# Aux_kicker.net
KiCad netlist of a schematic drawn in EAGLE
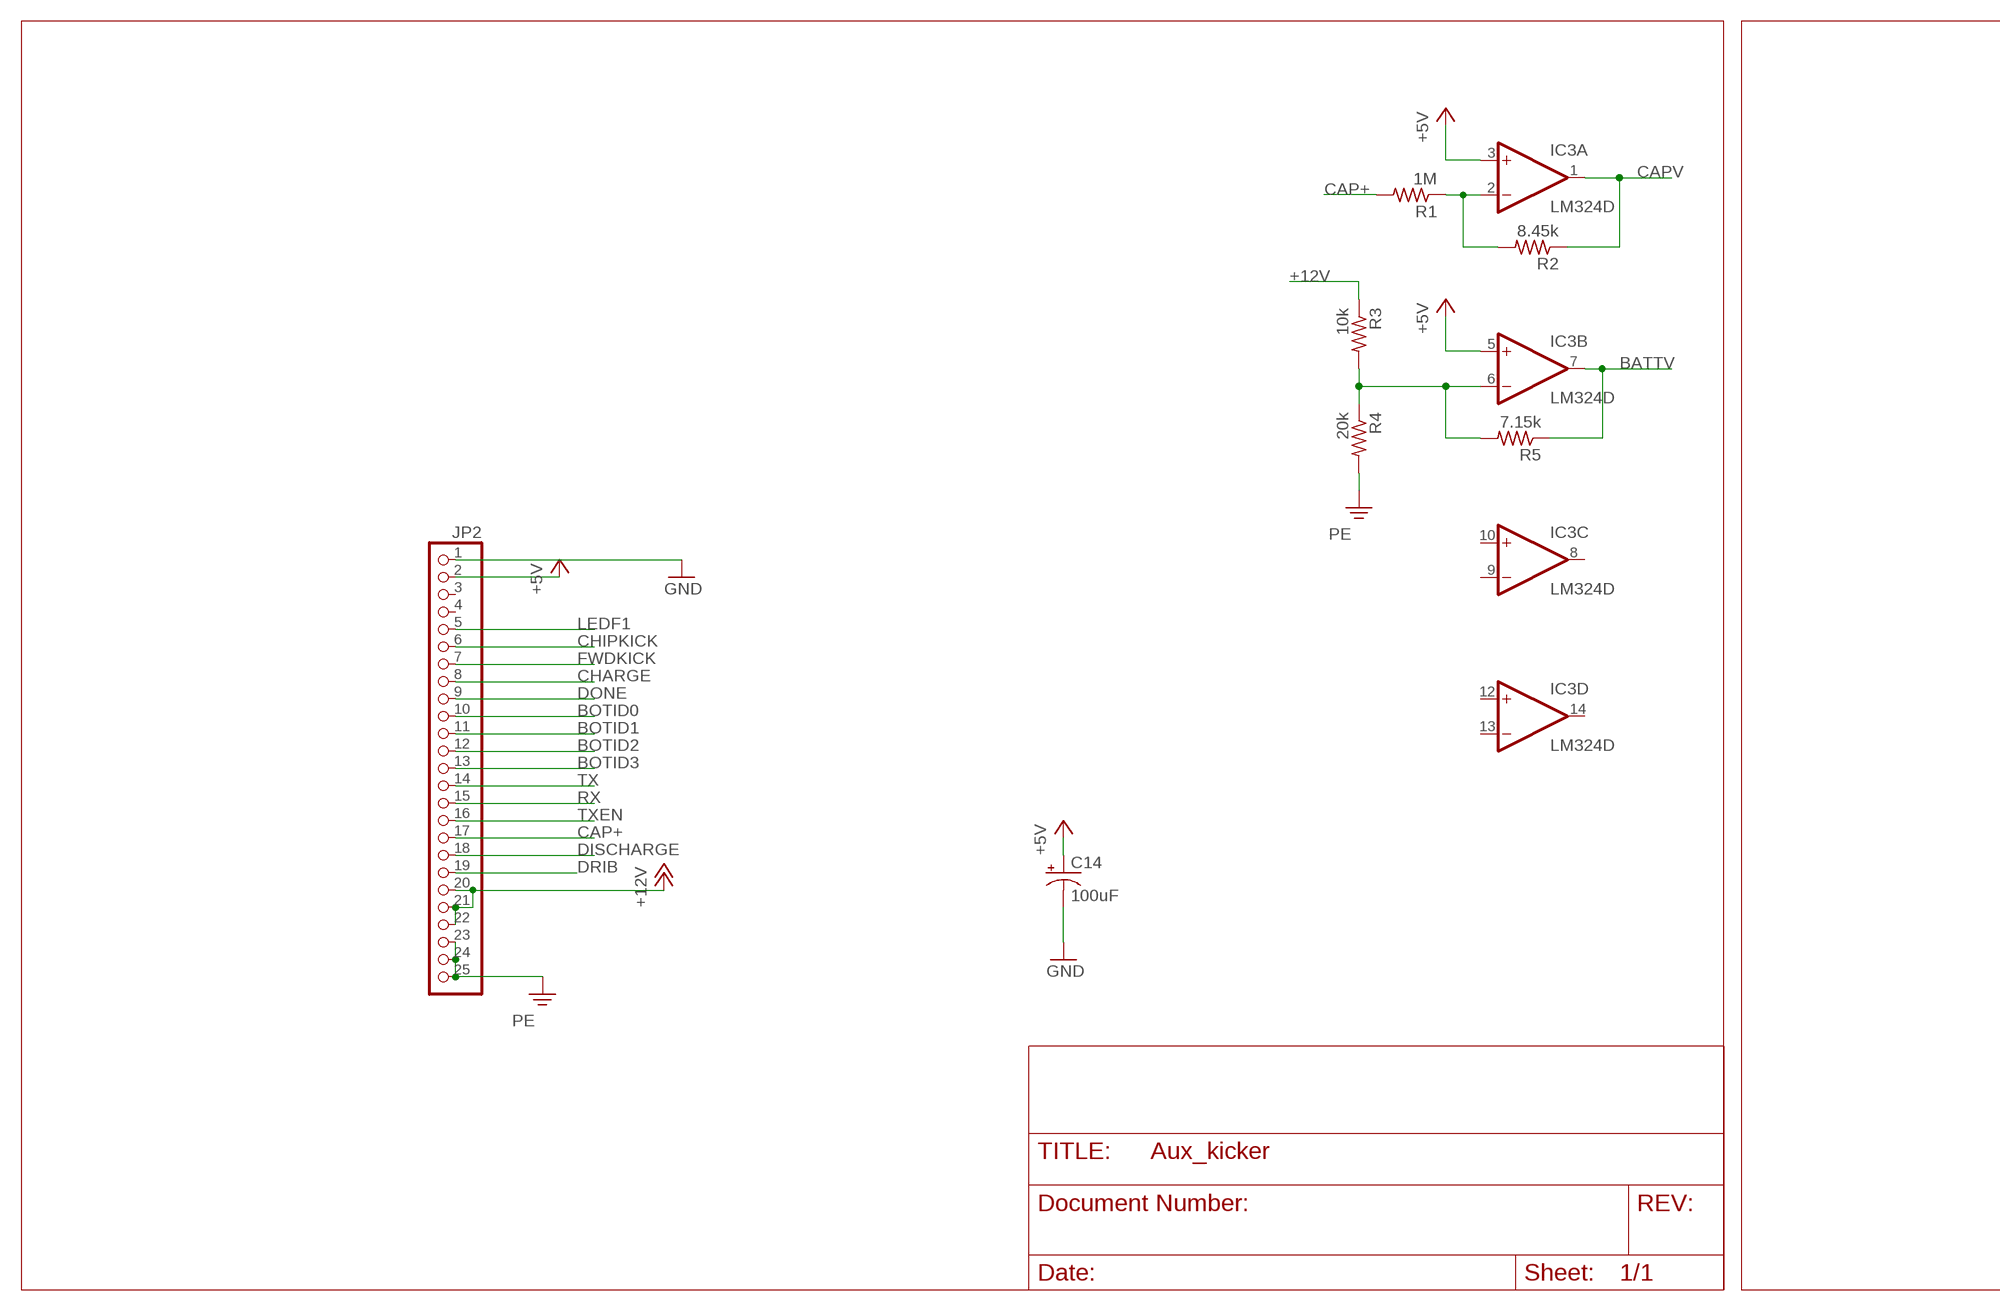
[diagram p0: schematic, sheet 1, part 1 of 2]
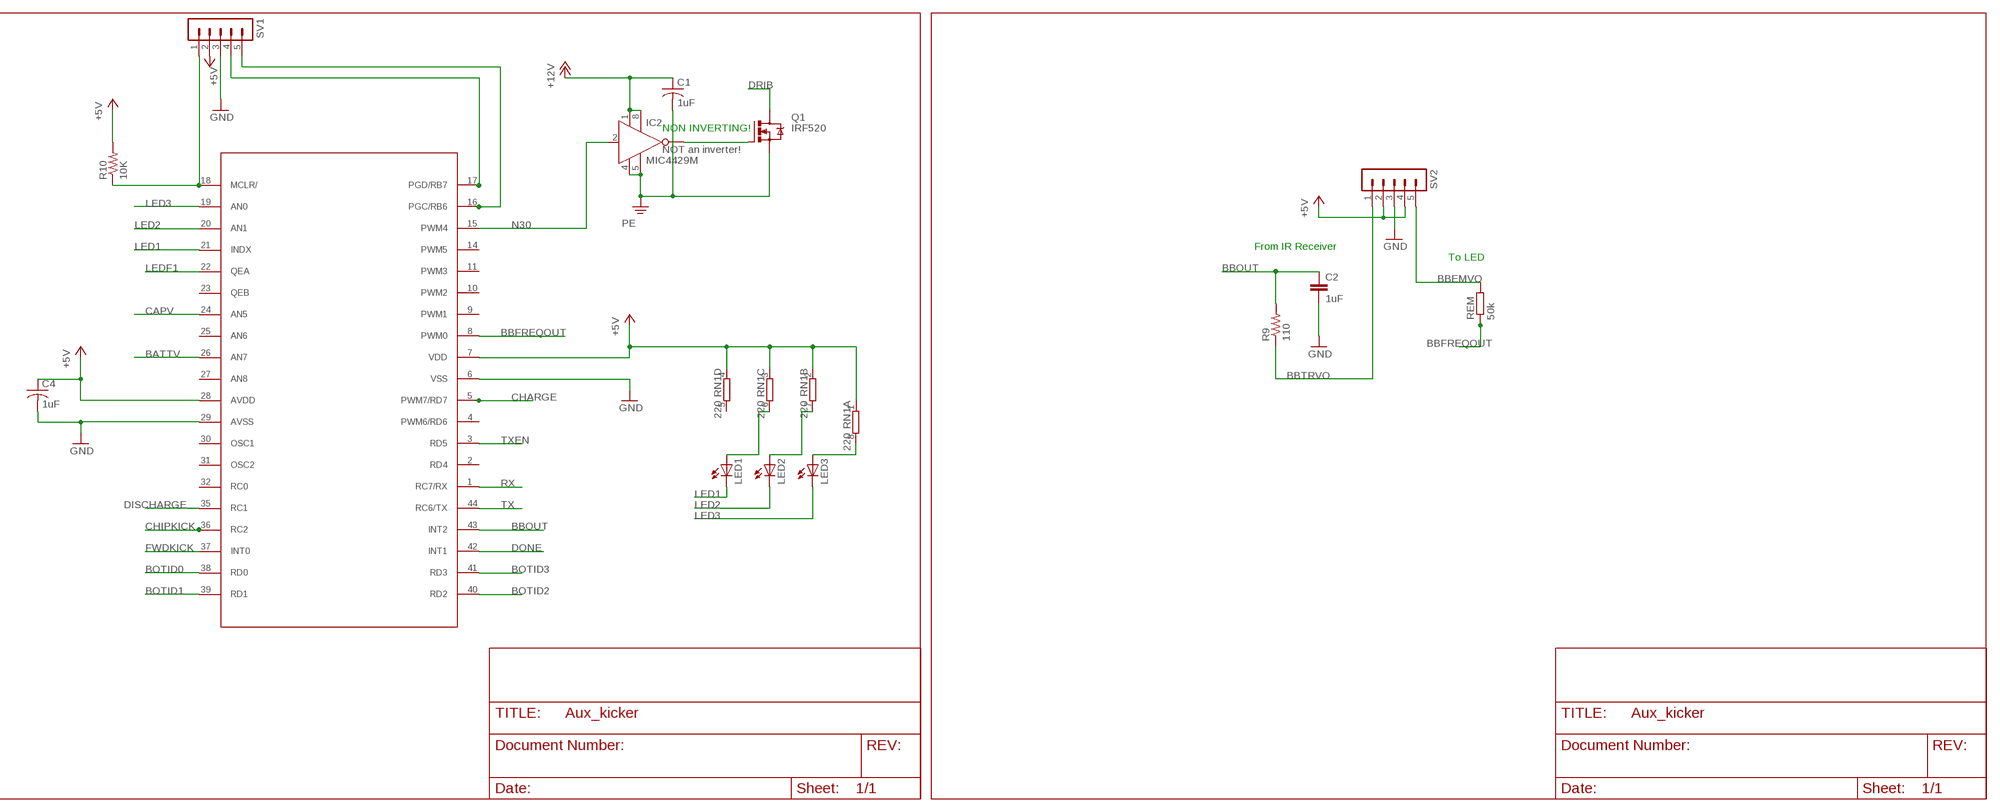
[diagram p1: schematic, sheet 1, part 2 of 2]

(export (version "E")
  (design (tool "Eeschema 10.0.6"))
  (components
    (comp (ref "C1")
      (value "1uF")
      (footprint "eagle-import:C0805")
      (libsource (lib "eagle-import") (part "C-USC0805"))
    )
    (comp (ref "C2")
      (value "1uF")
      (footprint "eagle-import:C0805")
      (libsource (lib "eagle-import") (part "C-EUC0805"))
    )
    (comp (ref "C4")
      (value "1uF")
      (footprint "eagle-import:C0805")
      (libsource (lib "eagle-import") (part "C-USC0805"))
    )
    (comp (ref "C14")
      (value "100uF")
      (footprint "eagle-import:E2,5-5")
      (libsource (lib "eagle-import") (part "CPOL-USE2.5-5"))
    )
    (comp (ref "IC1")
      (value "PIC18F4431S")
      (footprint "eagle-import:TQFP44")
      (libsource (lib "eagle-import") (part "PIC18F4431S"))
    )
    (comp (ref "IC2")
      (value "MIC4429M")
      (footprint "eagle-import:SO-08")
      (libsource (lib "eagle-import") (part "MIC4429M"))
    )
    (comp (ref "IC3")
      (value "LM324D")
      (footprint "eagle-import:SO14")
      (libsource (lib "eagle-import") (part "LM324D"))
    )
    (comp (ref "JP2")
      (value "PINHD-1X25")
      (footprint "eagle-import:1X25")
      (libsource (lib "eagle-import") (part "PINHD-1X25"))
    )
    (comp (ref "LED1")
      (value "LEDCHIPLED_0805")
      (footprint "eagle-import:CHIPLED_0805")
      (libsource (lib "eagle-import") (part "LEDCHIPLED_0805"))
    )
    (comp (ref "LED2")
      (value "LEDCHIPLED_0805")
      (footprint "eagle-import:CHIPLED_0805")
      (libsource (lib "eagle-import") (part "LEDCHIPLED_0805"))
    )
    (comp (ref "LED3")
      (value "LEDCHIPLED_0805")
      (footprint "eagle-import:CHIPLED_0805")
      (libsource (lib "eagle-import") (part "LEDCHIPLED_0805"))
    )
    (comp (ref "Q1")
      (value "IRF520")
      (footprint "eagle-import:TO220BV")
      (libsource (lib "eagle-import") (part "IRF520"))
    )
    (comp (ref "R1")
      (value "1M")
      (footprint "eagle-import:R0805")
      (libsource (lib "eagle-import") (part "R-US_R0805"))
    )
    (comp (ref "R2")
      (value "8.45k")
      (footprint "eagle-import:R0805")
      (libsource (lib "eagle-import") (part "R-US_R0805"))
    )
    (comp (ref "R3")
      (value "10k")
      (footprint "eagle-import:R0805")
      (libsource (lib "eagle-import") (part "R-US_R0805"))
    )
    (comp (ref "R4")
      (value "20k")
      (footprint "eagle-import:R0805")
      (libsource (lib "eagle-import") (part "R-US_R0805"))
    )
    (comp (ref "R5")
      (value "7.15k")
      (footprint "eagle-import:R0805")
      (libsource (lib "eagle-import") (part "R-US_R0805"))
    )
    (comp (ref "R9")
      (value "110")
      (footprint "eagle-import:R0805")
      (libsource (lib "eagle-import") (part "R-US_R0805"))
    )
    (comp (ref "R10")
      (value "10K")
      (footprint "eagle-import:R0805")
      (libsource (lib "eagle-import") (part "R-US_R0805"))
    )
    (comp (ref "REM")
      (value "50k")
      (footprint "eagle-import:R0805")
      (libsource (lib "eagle-import") (part "R-EU_R0805"))
    )
    (comp (ref "RN1")
      (value "220")
      (footprint "eagle-import:0603-ARC")
      (libsource (lib "eagle-import") (part "4R-N0603-ARC"))
    )
    (comp (ref "SV1")
      (value "MA05-1")
      (footprint "eagle-import:MA05-1")
      (libsource (lib "eagle-import") (part "MA05-1"))
    )
    (comp (ref "SV2")
      (value "MA05-1")
      (footprint "eagle-import:MA05-1")
      (libsource (lib "eagle-import") (part "MA05-1"))
    )
  )
  (nets
    (net (code "1") (name "+5V") (class "Default")
      (node (ref "C14") (pin "+") (pinfunction "+_+") (pintype "passive"))
      (node (ref "C4") (pin "1") (pinfunction "1_1") (pintype "passive"))
      (node (ref "IC1") (pin "28") (pinfunction "AVDD_28") (pintype "bidirectional"))
      (node (ref "IC1") (pin "7") (pinfunction "VDD_7") (pintype "bidirectional"))
      (node (ref "IC3") (pin "3") (pinfunction "+IN_3") (pintype "input"))
      (node (ref "IC3") (pin "5") (pinfunction "+IN_5") (pintype "input"))
      (node (ref "JP2") (pin "2") (pinfunction "2_2") (pintype "passive"))
      (node (ref "R10") (pin "2") (pinfunction "2_2") (pintype "passive"))
      (node (ref "RN1") (pin "1") (pinfunction "1_1") (pintype "passive"))
      (node (ref "RN1") (pin "2") (pinfunction "1_2") (pintype "passive"))
      (node (ref "RN1") (pin "3") (pinfunction "1_3") (pintype "passive"))
      (node (ref "RN1") (pin "4") (pinfunction "1_4") (pintype "passive"))
      (node (ref "SV1") (pin "2") (pinfunction "2_2") (pintype "passive"))
      (node (ref "SV2") (pin "2") (pinfunction "2_2") (pintype "passive"))
      (node (ref "SV2") (pin "4") (pinfunction "4_4") (pintype "passive"))
    )
    (net (code "2") (name "+12V") (class "Default")
      (node (ref "C1") (pin "1") (pinfunction "1_1") (pintype "passive"))
      (node (ref "IC2") (pin "1") (pinfunction "VS_1") (pintype "power_in"))
      (node (ref "IC2") (pin "8") (pinfunction "VS1_8") (pintype "power_in"))
      (node (ref "JP2") (pin "20") (pinfunction "20_20") (pintype "passive"))
      (node (ref "JP2") (pin "21") (pinfunction "21_21") (pintype "passive"))
      (node (ref "JP2") (pin "22") (pinfunction "22_22") (pintype "passive"))
      (node (ref "R3") (pin "1") (pinfunction "1_1") (pintype "passive"))
    )
    (net (code "3") (name "/BATTV") (class "Default")
      (node (ref "IC1") (pin "26") (pinfunction "AN7_26") (pintype "bidirectional"))
      (node (ref "IC3") (pin "7") (pinfunction "OUT_7") (pintype "output"))
      (node (ref "R5") (pin "1") (pinfunction "1_1") (pintype "passive"))
    )
    (net (code "4") (name "/BBEMVO") (class "Default")
      (node (ref "REM") (pin "2") (pinfunction "2_2") (pintype "passive"))
      (node (ref "SV2") (pin "5") (pinfunction "5_5") (pintype "passive"))
    )
    (net (code "5") (name "/BBFREQOUT") (class "Default")
      (node (ref "IC1") (pin "8") (pinfunction "PWM0_8") (pintype "bidirectional"))
      (node (ref "REM") (pin "1") (pinfunction "1_1") (pintype "passive"))
    )
    (net (code "6") (name "/BBOUT") (class "Default")
      (node (ref "C2") (pin "1") (pinfunction "1_1") (pintype "passive"))
      (node (ref "IC1") (pin "43") (pinfunction "INT2_43") (pintype "bidirectional"))
      (node (ref "R9") (pin "2") (pinfunction "2_2") (pintype "passive"))
    )
    (net (code "7") (name "/BBTRVO") (class "Default")
      (node (ref "R9") (pin "1") (pinfunction "1_1") (pintype "passive"))
      (node (ref "SV2") (pin "1") (pinfunction "1_1") (pintype "passive"))
    )
    (net (code "8") (name "/BOTID0") (class "Default")
      (node (ref "IC1") (pin "38") (pinfunction "RD0_38") (pintype "bidirectional"))
      (node (ref "JP2") (pin "10") (pinfunction "10_10") (pintype "passive"))
    )
    (net (code "9") (name "/BOTID1") (class "Default")
      (node (ref "IC1") (pin "39") (pinfunction "RD1_39") (pintype "bidirectional"))
      (node (ref "JP2") (pin "11") (pinfunction "11_11") (pintype "passive"))
    )
    (net (code "10") (name "/BOTID2") (class "Default")
      (node (ref "IC1") (pin "40") (pinfunction "RD2_40") (pintype "bidirectional"))
      (node (ref "JP2") (pin "12") (pinfunction "12_12") (pintype "passive"))
    )
    (net (code "11") (name "/BOTID3") (class "Default")
      (node (ref "IC1") (pin "41") (pinfunction "RD3_41") (pintype "bidirectional"))
      (node (ref "JP2") (pin "13") (pinfunction "13_13") (pintype "passive"))
    )
    (net (code "12") (name "/CAP+") (class "Default")
      (node (ref "JP2") (pin "17") (pinfunction "17_17") (pintype "passive"))
      (node (ref "R1") (pin "2") (pinfunction "2_2") (pintype "passive"))
    )
    (net (code "13") (name "/CAPV") (class "Default")
      (node (ref "IC1") (pin "24") (pinfunction "AN5_24") (pintype "bidirectional"))
      (node (ref "IC3") (pin "1") (pinfunction "OUT_1") (pintype "output"))
      (node (ref "R2") (pin "1") (pinfunction "1_1") (pintype "passive"))
    )
    (net (code "14") (name "/CHARGE") (class "Default")
      (node (ref "IC1") (pin "5") (pinfunction "PWM7/RD7_5") (pintype "bidirectional"))
      (node (ref "JP2") (pin "8") (pinfunction "8_8") (pintype "passive"))
    )
    (net (code "15") (name "/CHIPKICK") (class "Default")
      (node (ref "IC1") (pin "36") (pinfunction "RC2_36") (pintype "bidirectional"))
      (node (ref "JP2") (pin "6") (pinfunction "6_6") (pintype "passive"))
    )
    (net (code "16") (name "/DISCHARGE") (class "Default")
      (node (ref "IC1") (pin "35") (pinfunction "RC1_35") (pintype "bidirectional"))
      (node (ref "JP2") (pin "18") (pinfunction "18_18") (pintype "passive"))
    )
    (net (code "17") (name "/DONE") (class "Default")
      (node (ref "IC1") (pin "42") (pinfunction "INT1_42") (pintype "bidirectional"))
      (node (ref "JP2") (pin "9") (pinfunction "9_9") (pintype "passive"))
    )
    (net (code "18") (name "/DRIB") (class "Default")
      (node (ref "JP2") (pin "19") (pinfunction "19_19") (pintype "passive"))
      (node (ref "Q1") (pin "D") (pinfunction "D_D") (pintype "passive"))
    )
    (net (code "19") (name "/FWDKICK") (class "Default")
      (node (ref "IC1") (pin "37") (pinfunction "INT0_37") (pintype "bidirectional"))
      (node (ref "JP2") (pin "7") (pinfunction "7_7") (pintype "passive"))
    )
    (net (code "20") (name "/LED1") (class "Default")
      (node (ref "IC1") (pin "21") (pinfunction "INDX_21") (pintype "bidirectional"))
      (node (ref "LED1") (pin "C") (pinfunction "C_C") (pintype "passive"))
    )
    (net (code "21") (name "/LED2") (class "Default")
      (node (ref "IC1") (pin "20") (pinfunction "AN1_20") (pintype "bidirectional"))
      (node (ref "LED2") (pin "C") (pinfunction "C_C") (pintype "passive"))
    )
    (net (code "22") (name "/LED3") (class "Default")
      (node (ref "IC1") (pin "19") (pinfunction "AN0_19") (pintype "bidirectional"))
      (node (ref "LED3") (pin "C") (pinfunction "C_C") (pintype "passive"))
    )
    (net (code "23") (name "/LEDF1") (class "Default")
      (node (ref "IC1") (pin "22") (pinfunction "QEA_22") (pintype "bidirectional"))
      (node (ref "JP2") (pin "5") (pinfunction "5_5") (pintype "passive"))
    )
    (net (code "24") (name "/N30") (class "Default")
      (node (ref "IC1") (pin "15") (pinfunction "PWM4_15") (pintype "bidirectional"))
      (node (ref "IC2") (pin "2") (pinfunction "IN_2") (pintype "input"))
    )
    (net (code "25") (name "/RX") (class "Default")
      (node (ref "IC1") (pin "1") (pinfunction "RC7/RX_1") (pintype "bidirectional"))
      (node (ref "JP2") (pin "15") (pinfunction "15_15") (pintype "passive"))
    )
    (net (code "26") (name "/TX") (class "Default")
      (node (ref "IC1") (pin "44") (pinfunction "RC6/TX_44") (pintype "bidirectional"))
      (node (ref "JP2") (pin "14") (pinfunction "14_14") (pintype "passive"))
    )
    (net (code "27") (name "/TXEN") (class "Default")
      (node (ref "IC1") (pin "3") (pinfunction "RD5_3") (pintype "bidirectional"))
      (node (ref "JP2") (pin "16") (pinfunction "16_16") (pintype "passive"))
    )
    (net (code "28") (name "GND") (class "Default")
      (node (ref "C14") (pin "-") (pinfunction "-_-") (pintype "passive"))
      (node (ref "C2") (pin "2") (pinfunction "2_2") (pintype "passive"))
      (node (ref "C4") (pin "2") (pinfunction "2_2") (pintype "passive"))
      (node (ref "IC1") (pin "29") (pinfunction "AVSS_29") (pintype "bidirectional"))
      (node (ref "IC1") (pin "6") (pinfunction "VSS_6") (pintype "bidirectional"))
      (node (ref "JP2") (pin "1") (pinfunction "1_1") (pintype "passive"))
      (node (ref "SV1") (pin "3") (pinfunction "3_3") (pintype "passive"))
      (node (ref "SV2") (pin "3") (pinfunction "3_3") (pintype "passive"))
    )
    (net (code "29") (name "Net-(IC1-MCLR{slash})") (class "Default")
      (node (ref "IC1") (pin "18") (pinfunction "MCLR/_18") (pintype "bidirectional"))
      (node (ref "R10") (pin "1") (pinfunction "1_1") (pintype "passive"))
      (node (ref "SV1") (pin "1") (pinfunction "1_1") (pintype "passive"))
    )
    (net (code "30") (name "Net-(IC1-PGC{slash}RB6)") (class "Default")
      (node (ref "IC1") (pin "16") (pinfunction "PGC/RB6_16") (pintype "bidirectional"))
      (node (ref "SV1") (pin "5") (pinfunction "5_5") (pintype "passive"))
    )
    (net (code "31") (name "Net-(IC1-PGD{slash}RB7)") (class "Default")
      (node (ref "IC1") (pin "17") (pinfunction "PGD/RB7_17") (pintype "bidirectional"))
      (node (ref "SV1") (pin "4") (pinfunction "4_4") (pintype "passive"))
    )
    (net (code "32") (name "Net-(IC2-OUT-Pad6)") (class "Default")
      (node (ref "IC2") (pin "6") (pinfunction "OUT_6") (pintype "passive"))
      (node (ref "Q1") (pin "G") (pinfunction "G_G") (pintype "passive"))
    )
    (net (code "33") (name "Net-(IC3A--IN)") (class "Default")
      (node (ref "IC3") (pin "2") (pinfunction "-IN_2") (pintype "input"))
      (node (ref "R1") (pin "1") (pinfunction "1_1") (pintype "passive"))
      (node (ref "R2") (pin "2") (pinfunction "2_2") (pintype "passive"))
    )
    (net (code "34") (name "Net-(IC3B--IN)") (class "Default")
      (node (ref "IC3") (pin "6") (pinfunction "-IN_6") (pintype "input"))
      (node (ref "R3") (pin "2") (pinfunction "2_2") (pintype "passive"))
      (node (ref "R4") (pin "1") (pinfunction "1_1") (pintype "passive"))
      (node (ref "R5") (pin "2") (pinfunction "2_2") (pintype "passive"))
    )
    (net (code "35") (name "Net-(RN1A-2)") (class "Default")
      (node (ref "LED3") (pin "A") (pinfunction "A_A") (pintype "passive"))
      (node (ref "RN1") (pin "8") (pinfunction "2_8") (pintype "passive"))
    )
    (net (code "36") (name "Net-(RN1B-2)") (class "Default")
      (node (ref "LED2") (pin "A") (pinfunction "A_A") (pintype "passive"))
      (node (ref "RN1") (pin "7") (pinfunction "2_7") (pintype "passive"))
    )
    (net (code "37") (name "Net-(RN1C-2)") (class "Default")
      (node (ref "LED1") (pin "A") (pinfunction "A_A") (pintype "passive"))
      (node (ref "RN1") (pin "6") (pinfunction "2_6") (pintype "passive"))
    )
    (net (code "38") (name "PE") (class "Default")
      (node (ref "C1") (pin "2") (pinfunction "2_2") (pintype "passive"))
      (node (ref "IC2") (pin "4") (pinfunction "GND_4") (pintype "power_in"))
      (node (ref "IC2") (pin "5") (pinfunction "GND1_5") (pintype "power_in"))
      (node (ref "JP2") (pin "23") (pinfunction "23_23") (pintype "passive"))
      (node (ref "JP2") (pin "24") (pinfunction "24_24") (pintype "passive"))
      (node (ref "JP2") (pin "25") (pinfunction "25_25") (pintype "passive"))
      (node (ref "Q1") (pin "S") (pinfunction "S_S") (pintype "passive"))
      (node (ref "R4") (pin "2") (pinfunction "2_2") (pintype "passive"))
    )
    (net (code "39") (name "unconnected-(IC1-AN6-Pad25)") (class "Default")
      (node (ref "IC1") (pin "25") (pinfunction "AN6_25") (pintype "bidirectional"))
    )
    (net (code "40") (name "unconnected-(IC1-AN8-Pad27)") (class "Default")
      (node (ref "IC1") (pin "27") (pinfunction "AN8_27") (pintype "bidirectional"))
    )
    (net (code "41") (name "unconnected-(IC1-OSC1-Pad30)") (class "Default")
      (node (ref "IC1") (pin "30") (pinfunction "OSC1_30") (pintype "bidirectional"))
    )
    (net (code "42") (name "unconnected-(IC1-OSC2-Pad31)") (class "Default")
      (node (ref "IC1") (pin "31") (pinfunction "OSC2_31") (pintype "bidirectional"))
    )
    (net (code "43") (name "unconnected-(IC1-PWM1-Pad9)") (class "Default")
      (node (ref "IC1") (pin "9") (pinfunction "PWM1_9") (pintype "bidirectional"))
    )
    (net (code "44") (name "unconnected-(IC1-PWM2-Pad10)") (class "Default")
      (node (ref "IC1") (pin "10") (pinfunction "PWM2_10") (pintype "bidirectional"))
    )
    (net (code "45") (name "unconnected-(IC1-PWM3-Pad11)") (class "Default")
      (node (ref "IC1") (pin "11") (pinfunction "PWM3_11") (pintype "bidirectional"))
    )
    (net (code "46") (name "unconnected-(IC1-PWM5-Pad14)") (class "Default")
      (node (ref "IC1") (pin "14") (pinfunction "PWM5_14") (pintype "bidirectional"))
    )
    (net (code "47") (name "unconnected-(IC1-PWM6{slash}RD6-Pad4)") (class "Default")
      (node (ref "IC1") (pin "4") (pinfunction "PWM6/RD6_4") (pintype "bidirectional"))
    )
    (net (code "48") (name "unconnected-(IC1-QEB-Pad23)") (class "Default")
      (node (ref "IC1") (pin "23") (pinfunction "QEB_23") (pintype "bidirectional"))
    )
    (net (code "49") (name "unconnected-(IC1-RC0-Pad32)") (class "Default")
      (node (ref "IC1") (pin "32") (pinfunction "RC0_32") (pintype "bidirectional"))
    )
    (net (code "50") (name "unconnected-(IC1-RD4-Pad2)") (class "Default")
      (node (ref "IC1") (pin "2") (pinfunction "RD4_2") (pintype "bidirectional"))
    )
    (net (code "51") (name "unconnected-(IC2-OUT-Pad7)") (class "Default")
      (node (ref "IC2") (pin "7") (pinfunction "OUT_7") (pintype "passive"))
    )
    (net (code "52") (name "unconnected-(IC3C-+IN-Pad10)") (class "Default")
      (node (ref "IC3") (pin "10") (pinfunction "+IN_10") (pintype "input"))
    )
    (net (code "53") (name "unconnected-(IC3C--IN-Pad9)") (class "Default")
      (node (ref "IC3") (pin "9") (pinfunction "-IN_9") (pintype "input"))
    )
    (net (code "54") (name "unconnected-(IC3C-OUT-Pad8)") (class "Default")
      (node (ref "IC3") (pin "8") (pinfunction "OUT_8") (pintype "output"))
    )
    (net (code "55") (name "unconnected-(IC3D-+IN-Pad12)") (class "Default")
      (node (ref "IC3") (pin "12") (pinfunction "+IN_12") (pintype "input"))
    )
    (net (code "56") (name "unconnected-(IC3D--IN-Pad13)") (class "Default")
      (node (ref "IC3") (pin "13") (pinfunction "-IN_13") (pintype "input"))
    )
    (net (code "57") (name "unconnected-(IC3D-OUT-Pad14)") (class "Default")
      (node (ref "IC3") (pin "14") (pinfunction "OUT_14") (pintype "output"))
    )
    (net (code "58") (name "unconnected-(JP2-Pad3)") (class "Default")
      (node (ref "JP2") (pin "3") (pinfunction "3_3") (pintype "passive"))
    )
    (net (code "59") (name "unconnected-(JP2-Pad4)") (class "Default")
      (node (ref "JP2") (pin "4") (pinfunction "4_4") (pintype "passive"))
    )
    (net (code "60") (name "unconnected-(RN1D-2-Pad5)") (class "Default")
      (node (ref "RN1") (pin "5") (pinfunction "2_5") (pintype "passive"))
    )
  )
)
